# smartcar_shield.net
KiCad netlist of a schematic drawn in EAGLE
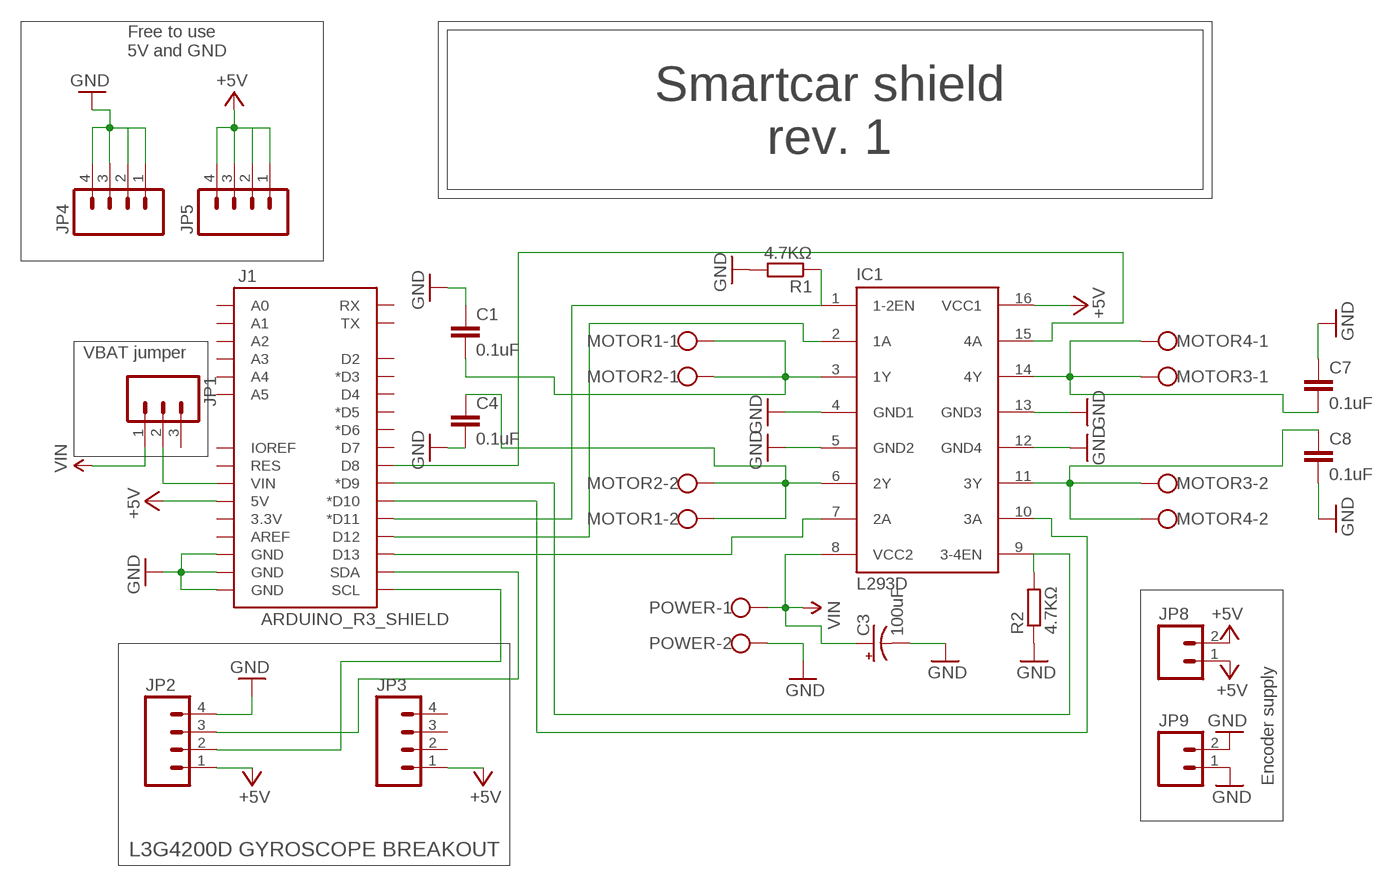
[diagram p0: schematic, sheet 1]

(export (version "E")
  (design (tool "Eeschema 10.0.6"))
  (components
    (comp (ref "C1")
      (value "0.1uF")
      (footprint "eagle-import:CAP-PTH-SMALL-KIT")
      (libsource (lib "eagle-import") (part "CAPKIT"))
    )
    (comp (ref "C3")
      (value "100uF")
      (footprint "eagle-import:CPOL-RADIAL-10UF-25V")
      (libsource (lib "eagle-import") (part "CAP_POLPTH2"))
    )
    (comp (ref "C4")
      (value "0.1uF")
      (footprint "eagle-import:CAP-PTH-SMALL-KIT")
      (libsource (lib "eagle-import") (part "CAPKIT"))
    )
    (comp (ref "C7")
      (value "0.1uF")
      (footprint "eagle-import:CAP-PTH-SMALL-KIT")
      (libsource (lib "eagle-import") (part "CAPKIT"))
    )
    (comp (ref "C8")
      (value "0.1uF")
      (footprint "eagle-import:CAP-PTH-SMALL-KIT")
      (libsource (lib "eagle-import") (part "CAPKIT"))
    )
    (comp (ref "IC1")
      (value "L293D")
      (footprint "eagle-import:DIL16")
      (libsource (lib "eagle-import") (part "L293D"))
    )
    (comp (ref "J1")
      (value "ARDUINO_R3_SHIELD")
      (footprint "eagle-import:UNO_R3_SHIELD")
      (libsource (lib "eagle-import") (part "ARDUINO_R3_SHIELD"))
    )
    (comp (ref "JP1")
      (value "M03PTH")
      (footprint "eagle-import:1X03")
      (libsource (lib "eagle-import") (part "M03PTH"))
    )
    (comp (ref "JP2")
      (value "M04NO_SILK_ALL_ROUND")
      (footprint "eagle-import:1X04_NO_SILK_ALL_ROUND")
      (libsource (lib "eagle-import") (part "M04NO_SILK_ALL_ROUND"))
    )
    (comp (ref "JP3")
      (value "M04NO_SILK_ALL_ROUND")
      (footprint "eagle-import:1X04_NO_SILK_ALL_ROUND")
      (libsource (lib "eagle-import") (part "M04NO_SILK_ALL_ROUND"))
    )
    (comp (ref "JP4")
      (value "M04NO_SILK_ALL_ROUND")
      (footprint "eagle-import:1X04_NO_SILK_ALL_ROUND")
      (libsource (lib "eagle-import") (part "M04NO_SILK_ALL_ROUND"))
    )
    (comp (ref "JP5")
      (value "M04NO_SILK_ALL_ROUND")
      (footprint "eagle-import:1X04_NO_SILK_ALL_ROUND")
      (libsource (lib "eagle-import") (part "M04NO_SILK_ALL_ROUND"))
    )
    (comp (ref "JP8")
      (value "M021X02_NO_SILK")
      (footprint "eagle-import:1X02_NO_SILK")
      (libsource (lib "eagle-import") (part "M021X02_NO_SILK"))
    )
    (comp (ref "JP9")
      (value "M021X02_NO_SILK")
      (footprint "eagle-import:1X02_NO_SILK")
      (libsource (lib "eagle-import") (part "M021X02_NO_SILK"))
    )
    (comp (ref "MOTOR1")
      (value "W237-102")
      (footprint "eagle-import:W237-102")
      (fields (field (name "MPN") "237-102"))
      (libsource (lib "eagle-import") (part "W237-102"))
    )
    (comp (ref "MOTOR2")
      (value "W237-102")
      (footprint "eagle-import:W237-102")
      (fields (field (name "MPN") "237-102"))
      (libsource (lib "eagle-import") (part "W237-102"))
    )
    (comp (ref "MOTOR3")
      (value "W237-102")
      (footprint "eagle-import:W237-102")
      (fields (field (name "MPN") "237-102"))
      (libsource (lib "eagle-import") (part "W237-102"))
    )
    (comp (ref "MOTOR4")
      (value "W237-102")
      (footprint "eagle-import:W237-102")
      (fields (field (name "MPN") "237-102"))
      (libsource (lib "eagle-import") (part "W237-102"))
    )
    (comp (ref "POWER")
      (value "W237-102")
      (footprint "eagle-import:W237-102")
      (fields (field (name "MPN") "237-102"))
      (libsource (lib "eagle-import") (part "W237-102"))
    )
    (comp (ref "R1")
      (value "4.7KΩ")
      (footprint "eagle-import:0207_10")
      (libsource (lib "eagle-import") (part "R-EU_0207/10"))
    )
    (comp (ref "R2")
      (value "4.7KΩ")
      (footprint "eagle-import:0207_10")
      (libsource (lib "eagle-import") (part "R-EU_0207/10"))
    )
  )
  (nets
    (net (code "1") (name "+5V") (class "Default")
      (node (ref "IC1") (pin "16") (pinfunction "VCC1_16") (pintype "power_in"))
      (node (ref "J1") (pin "5V") (pinfunction "5V_5V") (pintype "bidirectional"))
      (node (ref "JP2") (pin "1") (pinfunction "1_1") (pintype "passive"))
      (node (ref "JP3") (pin "1") (pinfunction "1_1") (pintype "passive"))
      (node (ref "JP5") (pin "1") (pinfunction "1_1") (pintype "passive"))
      (node (ref "JP5") (pin "2") (pinfunction "2_2") (pintype "passive"))
      (node (ref "JP5") (pin "3") (pinfunction "3_3") (pintype "passive"))
      (node (ref "JP5") (pin "4") (pinfunction "4_4") (pintype "passive"))
      (node (ref "JP8") (pin "1") (pinfunction "1_1") (pintype "passive"))
      (node (ref "JP8") (pin "2") (pinfunction "2_2") (pintype "passive"))
    )
    (net (code "2") (name "12V") (class "Default")
      (node (ref "C3") (pin "1") (pinfunction "+_1") (pintype "passive"))
      (node (ref "IC1") (pin "8") (pinfunction "VCC2_8") (pintype "power_in"))
      (node (ref "JP1") (pin "1") (pinfunction "1_1") (pintype "passive"))
      (node (ref "POWER") (pin "1") (pinfunction "KL_1") (pintype "passive"))
    )
    (net (code "3") (name "GND") (class "Default")
      (node (ref "C1") (pin "1") (pinfunction "1_1") (pintype "passive"))
      (node (ref "C3") (pin "2") (pinfunction "-_2") (pintype "passive"))
      (node (ref "C4") (pin "2") (pinfunction "2_2") (pintype "passive"))
      (node (ref "C7") (pin "1") (pinfunction "1_1") (pintype "passive"))
      (node (ref "C8") (pin "2") (pinfunction "2_2") (pintype "passive"))
      (node (ref "IC1") (pin "12") (pinfunction "GND4_12") (pintype "power_in"))
      (node (ref "IC1") (pin "13") (pinfunction "GND3_13") (pintype "power_in"))
      (node (ref "IC1") (pin "4") (pinfunction "GND1_4") (pintype "power_in"))
      (node (ref "IC1") (pin "5") (pinfunction "GND2_5") (pintype "power_in"))
      (node (ref "J1") (pin "GND@0") (pinfunction "GND_GND@0") (pintype "bidirectional"))
      (node (ref "J1") (pin "GND@1") (pinfunction "GND_GND@1") (pintype "bidirectional"))
      (node (ref "J1") (pin "GND@2") (pinfunction "GND_GND@2") (pintype "bidirectional"))
      (node (ref "JP2") (pin "4") (pinfunction "4_4") (pintype "passive"))
      (node (ref "JP4") (pin "1") (pinfunction "1_1") (pintype "passive"))
      (node (ref "JP4") (pin "2") (pinfunction "2_2") (pintype "passive"))
      (node (ref "JP4") (pin "3") (pinfunction "3_3") (pintype "passive"))
      (node (ref "JP4") (pin "4") (pinfunction "4_4") (pintype "passive"))
      (node (ref "JP9") (pin "1") (pinfunction "1_1") (pintype "passive"))
      (node (ref "JP9") (pin "2") (pinfunction "2_2") (pintype "passive"))
      (node (ref "POWER") (pin "2") (pinfunction "KL_2") (pintype "passive"))
      (node (ref "R1") (pin "2") (pinfunction "2_2") (pintype "passive"))
      (node (ref "R2") (pin "1") (pinfunction "1_1") (pintype "passive"))
    )
    (net (code "4") (name "Net-(IC1-1-2EN)") (class "Default")
      (node (ref "IC1") (pin "1") (pinfunction "1-2EN_1") (pintype "input"))
      (node (ref "J1") (pin "D11") (pinfunction "*D11_D11") (pintype "bidirectional"))
      (node (ref "R1") (pin "1") (pinfunction "1_1") (pintype "passive"))
    )
    (net (code "5") (name "Net-(IC1-1A)") (class "Default")
      (node (ref "IC1") (pin "2") (pinfunction "1A_2") (pintype "input"))
      (node (ref "J1") (pin "D12") (pinfunction "D12_D12") (pintype "bidirectional"))
    )
    (net (code "6") (name "Net-(IC1-1Y)") (class "Default")
      (node (ref "C1") (pin "2") (pinfunction "2_2") (pintype "passive"))
      (node (ref "IC1") (pin "3") (pinfunction "1Y_3") (pintype "output"))
      (node (ref "MOTOR1") (pin "1") (pinfunction "KL_1") (pintype "passive"))
      (node (ref "MOTOR2") (pin "1") (pinfunction "KL_1") (pintype "passive"))
    )
    (net (code "7") (name "Net-(IC1-2A)") (class "Default")
      (node (ref "IC1") (pin "7") (pinfunction "2A_7") (pintype "input"))
      (node (ref "J1") (pin "D13") (pinfunction "D13_D13") (pintype "bidirectional"))
    )
    (net (code "8") (name "Net-(IC1-2Y)") (class "Default")
      (node (ref "C4") (pin "1") (pinfunction "1_1") (pintype "passive"))
      (node (ref "IC1") (pin "6") (pinfunction "2Y_6") (pintype "output"))
      (node (ref "MOTOR1") (pin "2") (pinfunction "KL_2") (pintype "passive"))
      (node (ref "MOTOR2") (pin "2") (pinfunction "KL_2") (pintype "passive"))
    )
    (net (code "9") (name "Net-(IC1-3-4EN)") (class "Default")
      (node (ref "IC1") (pin "9") (pinfunction "3-4EN_9") (pintype "input"))
      (node (ref "J1") (pin "D9") (pinfunction "*D9_D9") (pintype "bidirectional"))
      (node (ref "R2") (pin "2") (pinfunction "2_2") (pintype "passive"))
    )
    (net (code "10") (name "Net-(IC1-3A)") (class "Default")
      (node (ref "IC1") (pin "10") (pinfunction "3A_10") (pintype "input"))
      (node (ref "J1") (pin "D10") (pinfunction "*D10_D10") (pintype "bidirectional"))
    )
    (net (code "11") (name "Net-(IC1-3Y)") (class "Default")
      (node (ref "C8") (pin "1") (pinfunction "1_1") (pintype "passive"))
      (node (ref "IC1") (pin "11") (pinfunction "3Y_11") (pintype "output"))
      (node (ref "MOTOR3") (pin "2") (pinfunction "KL_2") (pintype "passive"))
      (node (ref "MOTOR4") (pin "2") (pinfunction "KL_2") (pintype "passive"))
    )
    (net (code "12") (name "Net-(IC1-4A)") (class "Default")
      (node (ref "IC1") (pin "15") (pinfunction "4A_15") (pintype "input"))
      (node (ref "J1") (pin "D8") (pinfunction "D8_D8") (pintype "bidirectional"))
    )
    (net (code "13") (name "Net-(IC1-4Y)") (class "Default")
      (node (ref "C7") (pin "2") (pinfunction "2_2") (pintype "passive"))
      (node (ref "IC1") (pin "14") (pinfunction "4Y_14") (pintype "output"))
      (node (ref "MOTOR3") (pin "1") (pinfunction "KL_1") (pintype "passive"))
      (node (ref "MOTOR4") (pin "1") (pinfunction "KL_1") (pintype "passive"))
    )
    (net (code "14") (name "Net-(J1-PadSCL)") (class "Default")
      (node (ref "J1") (pin "SCL") (pinfunction "SCL_SCL") (pintype "bidirectional"))
      (node (ref "JP2") (pin "2") (pinfunction "2_2") (pintype "passive"))
    )
    (net (code "15") (name "Net-(J1-PadSDA)") (class "Default")
      (node (ref "J1") (pin "SDA") (pinfunction "SDA_SDA") (pintype "bidirectional"))
      (node (ref "JP2") (pin "3") (pinfunction "3_3") (pintype "passive"))
    )
    (net (code "16") (name "Net-(J1-PadVIN)") (class "Default")
      (node (ref "J1") (pin "VIN") (pinfunction "VIN_VIN") (pintype "bidirectional"))
      (node (ref "JP1") (pin "2") (pinfunction "2_2") (pintype "passive"))
    )
    (net (code "17") (name "unconnected-(J1-*D3-PadD3)") (class "Default")
      (node (ref "J1") (pin "D3") (pinfunction "*D3_D3") (pintype "bidirectional"))
    )
    (net (code "18") (name "unconnected-(J1-*D5-PadD5)") (class "Default")
      (node (ref "J1") (pin "D5") (pinfunction "*D5_D5") (pintype "bidirectional"))
    )
    (net (code "19") (name "unconnected-(J1-*D6-PadD6)") (class "Default")
      (node (ref "J1") (pin "D6") (pinfunction "*D6_D6") (pintype "bidirectional"))
    )
    (net (code "20") (name "unconnected-(J1-Pad3.3V)") (class "Default")
      (node (ref "J1") (pin "3.3V") (pinfunction "3.3V_3.3V") (pintype "bidirectional"))
    )
    (net (code "21") (name "unconnected-(J1-PadA0)") (class "Default")
      (node (ref "J1") (pin "A0") (pinfunction "A0_A0") (pintype "bidirectional"))
    )
    (net (code "22") (name "unconnected-(J1-PadA1)") (class "Default")
      (node (ref "J1") (pin "A1") (pinfunction "A1_A1") (pintype "bidirectional"))
    )
    (net (code "23") (name "unconnected-(J1-PadA2)") (class "Default")
      (node (ref "J1") (pin "A2") (pinfunction "A2_A2") (pintype "bidirectional"))
    )
    (net (code "24") (name "unconnected-(J1-PadA3)") (class "Default")
      (node (ref "J1") (pin "A3") (pinfunction "A3_A3") (pintype "bidirectional"))
    )
    (net (code "25") (name "unconnected-(J1-PadA4)") (class "Default")
      (node (ref "J1") (pin "A4") (pinfunction "A4_A4") (pintype "bidirectional"))
    )
    (net (code "26") (name "unconnected-(J1-PadA5)") (class "Default")
      (node (ref "J1") (pin "A5") (pinfunction "A5_A5") (pintype "bidirectional"))
    )
    (net (code "27") (name "unconnected-(J1-PadAREF)") (class "Default")
      (node (ref "J1") (pin "AREF") (pinfunction "AREF_AREF") (pintype "bidirectional"))
    )
    (net (code "28") (name "unconnected-(J1-PadD2)") (class "Default")
      (node (ref "J1") (pin "D2") (pinfunction "D2_D2") (pintype "bidirectional"))
    )
    (net (code "29") (name "unconnected-(J1-PadD4)") (class "Default")
      (node (ref "J1") (pin "D4") (pinfunction "D4_D4") (pintype "bidirectional"))
    )
    (net (code "30") (name "unconnected-(J1-PadD7)") (class "Default")
      (node (ref "J1") (pin "D7") (pinfunction "D7_D7") (pintype "bidirectional"))
    )
    (net (code "31") (name "unconnected-(J1-PadIOREF)") (class "Default")
      (node (ref "J1") (pin "IOREF") (pinfunction "IOREF_IOREF") (pintype "bidirectional"))
    )
    (net (code "32") (name "unconnected-(J1-PadRES)") (class "Default")
      (node (ref "J1") (pin "RES") (pinfunction "RES_RES") (pintype "bidirectional"))
    )
    (net (code "33") (name "unconnected-(J1-PadRX)") (class "Default")
      (node (ref "J1") (pin "RX") (pinfunction "RX_RX") (pintype "bidirectional"))
    )
    (net (code "34") (name "unconnected-(J1-PadTX)") (class "Default")
      (node (ref "J1") (pin "TX") (pinfunction "TX_TX") (pintype "bidirectional"))
    )
    (net (code "35") (name "unconnected-(JP1-Pad3)") (class "Default")
      (node (ref "JP1") (pin "3") (pinfunction "3_3") (pintype "passive"))
    )
    (net (code "36") (name "unconnected-(JP3-Pad2)") (class "Default")
      (node (ref "JP3") (pin "2") (pinfunction "2_2") (pintype "passive"))
    )
    (net (code "37") (name "unconnected-(JP3-Pad3)") (class "Default")
      (node (ref "JP3") (pin "3") (pinfunction "3_3") (pintype "passive"))
    )
    (net (code "38") (name "unconnected-(JP3-Pad4)") (class "Default")
      (node (ref "JP3") (pin "4") (pinfunction "4_4") (pintype "passive"))
    )
  )
)
